# FPGA_QDRII.net
KiCad netlist of a schematic drawn in Altium Designer
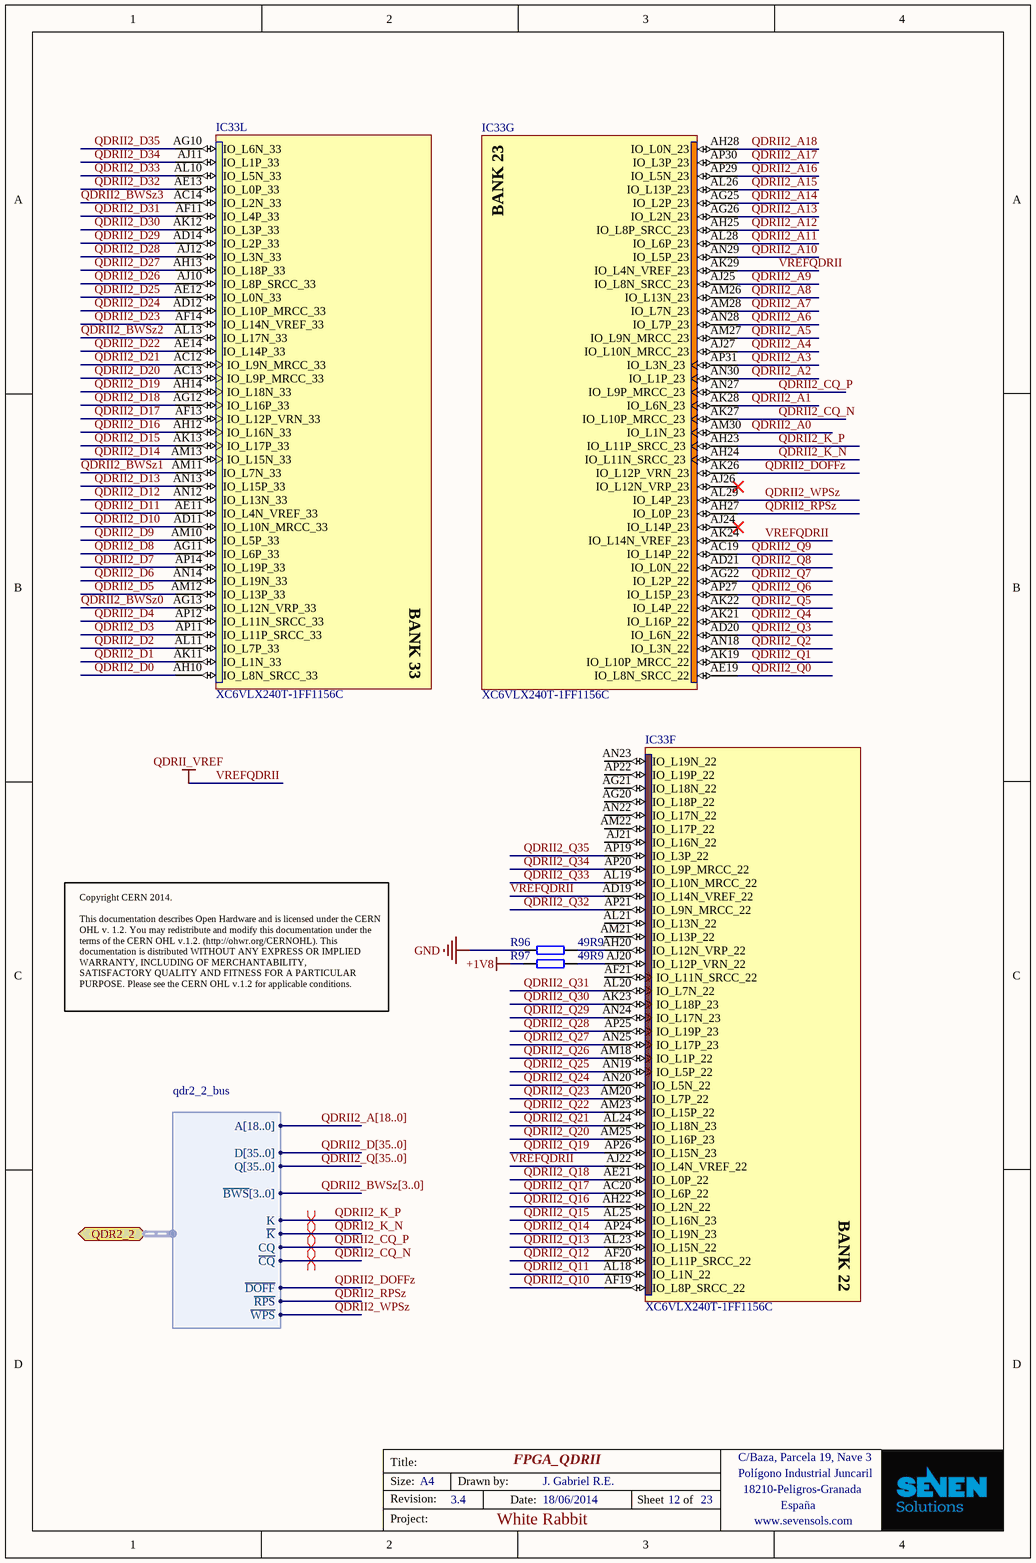
[diagram p0: FPGA_QDRII.SchDoc]

(export (version "E")
  (design (tool "Eeschema 10.0.6"))
  (components
    (comp (ref "IC33")
      (value "XC6VLX240T-1FF1156C")
      (footprint "FF1156")
      (fields (field (name "PUBLISHER") "Altium Limited"))
      (libsource (lib "") (part "XC6VLX240T-1FF1156C_1"))
    )
    (comp (ref "R96")
      (value "49R9")
      (footprint "0402")
      (description "SMD Resistor")
      (fields (field (name "TOLERANCE") "±1%") (field (name "Comment") "49R9 (not mounted)"))
      (libsource (lib "wr_switch") (part "RES_SMD"))
    )
    (comp (ref "R97")
      (value "49R9")
      (footprint "0402")
      (description "SMD Resistor")
      (fields (field (name "TOLERANCE") "±1%") (field (name "Comment") "49R9 (not mounted)"))
      (libsource (lib "wr_switch") (part "RES_SMD"))
    )
  )
  (nets
    (net (code "2") (name "+1V8") (class "Default")
      (node (ref "R97") (pin "2") (pinfunction "2_2") (pintype "passive"))
    )
    (net (code "4") (name "/QDRII2_A0") (class "Default")
      (node (ref "IC33") (pin "AM30") (pinfunction "IO_L1N_23_AM30") (pintype "bidirectional"))
    )
    (net (code "5") (name "/QDRII2_A1") (class "Default")
      (node (ref "IC33") (pin "AK28") (pinfunction "IO_L6N_23_AK28") (pintype "bidirectional"))
    )
    (net (code "6") (name "/QDRII2_A2") (class "Default")
      (node (ref "IC33") (pin "AN30") (pinfunction "IO_L1P_23_AN30") (pintype "bidirectional"))
    )
    (net (code "7") (name "/QDRII2_A3") (class "Default")
      (node (ref "IC33") (pin "AP31") (pinfunction "IO_L3N_23_AP31") (pintype "bidirectional"))
    )
    (net (code "8") (name "/QDRII2_A4") (class "Default")
      (node (ref "IC33") (pin "AJ27") (pinfunction "IO_L10N_MRCC_23_AJ27") (pintype "bidirectional"))
    )
    (net (code "9") (name "/QDRII2_A5") (class "Default")
      (node (ref "IC33") (pin "AM27") (pinfunction "IO_L9N_MRCC_23_AM27") (pintype "bidirectional"))
    )
    (net (code "10") (name "/QDRII2_A6") (class "Default")
      (node (ref "IC33") (pin "AN28") (pinfunction "IO_L7P_23_AN28") (pintype "bidirectional"))
    )
    (net (code "11") (name "/QDRII2_A7") (class "Default")
      (node (ref "IC33") (pin "AM28") (pinfunction "IO_L7N_23_AM28") (pintype "bidirectional"))
    )
    (net (code "12") (name "/QDRII2_A8") (class "Default")
      (node (ref "IC33") (pin "AM26") (pinfunction "IO_L13N_23_AM26") (pintype "bidirectional"))
    )
    (net (code "13") (name "/QDRII2_A9") (class "Default")
      (node (ref "IC33") (pin "AJ25") (pinfunction "IO_L8N_SRCC_23_AJ25") (pintype "bidirectional"))
    )
    (net (code "14") (name "/QDRII2_A10") (class "Default")
      (node (ref "IC33") (pin "AN29") (pinfunction "IO_L5P_23_AN29") (pintype "bidirectional"))
    )
    (net (code "15") (name "/QDRII2_A11") (class "Default")
      (node (ref "IC33") (pin "AL28") (pinfunction "IO_L6P_23_AL28") (pintype "bidirectional"))
    )
    (net (code "16") (name "/QDRII2_A12") (class "Default")
      (node (ref "IC33") (pin "AH25") (pinfunction "IO_L8P_SRCC_23_AH25") (pintype "bidirectional"))
    )
    (net (code "17") (name "/QDRII2_A13") (class "Default")
      (node (ref "IC33") (pin "AG26") (pinfunction "IO_L2N_23_AG26") (pintype "bidirectional"))
    )
    (net (code "18") (name "/QDRII2_A14") (class "Default")
      (node (ref "IC33") (pin "AG25") (pinfunction "IO_L2P_23_AG25") (pintype "bidirectional"))
    )
    (net (code "19") (name "/QDRII2_A15") (class "Default")
      (node (ref "IC33") (pin "AL26") (pinfunction "IO_L13P_23_AL26") (pintype "bidirectional"))
    )
    (net (code "20") (name "/QDRII2_A16") (class "Default")
      (node (ref "IC33") (pin "AP29") (pinfunction "IO_L5N_23_AP29") (pintype "bidirectional"))
    )
    (net (code "21") (name "/QDRII2_A17") (class "Default")
      (node (ref "IC33") (pin "AP30") (pinfunction "IO_L3P_23_AP30") (pintype "bidirectional"))
    )
    (net (code "22") (name "/QDRII2_A18") (class "Default")
      (node (ref "IC33") (pin "AH28") (pinfunction "IO_L0N_23_AH28") (pintype "bidirectional"))
    )
    (net (code "24") (name "/QDRII2_BWSz0") (class "Default")
      (node (ref "IC33") (pin "AG13") (pinfunction "IO_L12N_VRP_33_AG13") (pintype "bidirectional"))
    )
    (net (code "25") (name "/QDRII2_BWSz1") (class "Default")
      (node (ref "IC33") (pin "AM11") (pinfunction "IO_L7N_33_AM11") (pintype "bidirectional"))
    )
    (net (code "26") (name "/QDRII2_BWSz2") (class "Default")
      (node (ref "IC33") (pin "AL13") (pinfunction "IO_L17N_33_AL13") (pintype "bidirectional"))
    )
    (net (code "27") (name "/QDRII2_BWSz3") (class "Default")
      (node (ref "IC33") (pin "AC14") (pinfunction "IO_L2N_33_AC14") (pintype "bidirectional"))
    )
    (net (code "28") (name "/QDRII2_CQ_N") (class "Default")
      (node (ref "IC33") (pin "AK27") (pinfunction "IO_L10P_MRCC_23_AK27") (pintype "bidirectional"))
    )
    (net (code "29") (name "/QDRII2_CQ_P") (class "Default")
      (node (ref "IC33") (pin "AN27") (pinfunction "IO_L9P_MRCC_23_AN27") (pintype "bidirectional"))
    )
    (net (code "30") (name "/QDRII2_D0") (class "Default")
      (node (ref "IC33") (pin "AH10") (pinfunction "IO_L8N_SRCC_33_AH10") (pintype "bidirectional"))
    )
    (net (code "31") (name "/QDRII2_D1") (class "Default")
      (node (ref "IC33") (pin "AK11") (pinfunction "IO_L1N_33_AK11") (pintype "bidirectional"))
    )
    (net (code "32") (name "/QDRII2_D2") (class "Default")
      (node (ref "IC33") (pin "AL11") (pinfunction "IO_L7P_33_AL11") (pintype "bidirectional"))
    )
    (net (code "33") (name "/QDRII2_D3") (class "Default")
      (node (ref "IC33") (pin "AP11") (pinfunction "IO_L11P_SRCC_33_AP11") (pintype "bidirectional"))
    )
    (net (code "34") (name "/QDRII2_D4") (class "Default")
      (node (ref "IC33") (pin "AP12") (pinfunction "IO_L11N_SRCC_33_AP12") (pintype "bidirectional"))
    )
    (net (code "35") (name "/QDRII2_D5") (class "Default")
      (node (ref "IC33") (pin "AM12") (pinfunction "IO_L13P_33_AM12") (pintype "bidirectional"))
    )
    (net (code "36") (name "/QDRII2_D6") (class "Default")
      (node (ref "IC33") (pin "AN14") (pinfunction "IO_L19N_33_AN14") (pintype "bidirectional"))
    )
    (net (code "37") (name "/QDRII2_D7") (class "Default")
      (node (ref "IC33") (pin "AP14") (pinfunction "IO_L19P_33_AP14") (pintype "bidirectional"))
    )
    (net (code "38") (name "/QDRII2_D8") (class "Default")
      (node (ref "IC33") (pin "AG11") (pinfunction "IO_L6P_33_AG11") (pintype "bidirectional"))
    )
    (net (code "39") (name "/QDRII2_D9") (class "Default")
      (node (ref "IC33") (pin "AM10") (pinfunction "IO_L5P_33_AM10") (pintype "bidirectional"))
    )
    (net (code "40") (name "/QDRII2_D10") (class "Default")
      (node (ref "IC33") (pin "AD11") (pinfunction "IO_L10N_MRCC_33_AD11") (pintype "bidirectional"))
    )
    (net (code "41") (name "/QDRII2_D11") (class "Default")
      (node (ref "IC33") (pin "AE11") (pinfunction "IO_L4N_VREF_33_AE11") (pintype "bidirectional"))
    )
    (net (code "42") (name "/QDRII2_D12") (class "Default")
      (node (ref "IC33") (pin "AN12") (pinfunction "IO_L13N_33_AN12") (pintype "bidirectional"))
    )
    (net (code "43") (name "/QDRII2_D13") (class "Default")
      (node (ref "IC33") (pin "AN13") (pinfunction "IO_L15P_33_AN13") (pintype "bidirectional"))
    )
    (net (code "44") (name "/QDRII2_D14") (class "Default")
      (node (ref "IC33") (pin "AM13") (pinfunction "IO_L15N_33_AM13") (pintype "bidirectional"))
    )
    (net (code "45") (name "/QDRII2_D15") (class "Default")
      (node (ref "IC33") (pin "AK13") (pinfunction "IO_L17P_33_AK13") (pintype "bidirectional"))
    )
    (net (code "46") (name "/QDRII2_D16") (class "Default")
      (node (ref "IC33") (pin "AH12") (pinfunction "IO_L16N_33_AH12") (pintype "bidirectional"))
    )
    (net (code "47") (name "/QDRII2_D17") (class "Default")
      (node (ref "IC33") (pin "AF13") (pinfunction "IO_L12P_VRN_33_AF13") (pintype "bidirectional"))
    )
    (net (code "48") (name "/QDRII2_D18") (class "Default")
      (node (ref "IC33") (pin "AG12") (pinfunction "IO_L16P_33_AG12") (pintype "bidirectional"))
    )
    (net (code "49") (name "/QDRII2_D19") (class "Default")
      (node (ref "IC33") (pin "AH14") (pinfunction "IO_L18N_33_AH14") (pintype "bidirectional"))
    )
    (net (code "50") (name "/QDRII2_D20") (class "Default")
      (node (ref "IC33") (pin "AC13") (pinfunction "IO_L9P_MRCC_33_AC13") (pintype "bidirectional"))
    )
    (net (code "51") (name "/QDRII2_D21") (class "Default")
      (node (ref "IC33") (pin "AC12") (pinfunction "IO_L9N_MRCC_33_AC12") (pintype "bidirectional"))
    )
    (net (code "52") (name "/QDRII2_D22") (class "Default")
      (node (ref "IC33") (pin "AE14") (pinfunction "IO_L14P_33_AE14") (pintype "bidirectional"))
    )
    (net (code "53") (name "/QDRII2_D23") (class "Default")
      (node (ref "IC33") (pin "AF14") (pinfunction "IO_L14N_VREF_33_AF14") (pintype "bidirectional"))
    )
    (net (code "54") (name "/QDRII2_D24") (class "Default")
      (node (ref "IC33") (pin "AD12") (pinfunction "IO_L10P_MRCC_33_AD12") (pintype "bidirectional"))
    )
    (net (code "55") (name "/QDRII2_D25") (class "Default")
      (node (ref "IC33") (pin "AE12") (pinfunction "IO_L0N_33_AE12") (pintype "bidirectional"))
    )
    (net (code "56") (name "/QDRII2_D26") (class "Default")
      (node (ref "IC33") (pin "AJ10") (pinfunction "IO_L8P_SRCC_33_AJ10") (pintype "bidirectional"))
    )
    (net (code "57") (name "/QDRII2_D27") (class "Default")
      (node (ref "IC33") (pin "AH13") (pinfunction "IO_L18P_33_AH13") (pintype "bidirectional"))
    )
    (net (code "58") (name "/QDRII2_D28") (class "Default")
      (node (ref "IC33") (pin "AJ12") (pinfunction "IO_L3N_33_AJ12") (pintype "bidirectional"))
    )
    (net (code "59") (name "/QDRII2_D29") (class "Default")
      (node (ref "IC33") (pin "AD14") (pinfunction "IO_L2P_33_AD14") (pintype "bidirectional"))
    )
    (net (code "60") (name "/QDRII2_D30") (class "Default")
      (node (ref "IC33") (pin "AK12") (pinfunction "IO_L3P_33_AK12") (pintype "bidirectional"))
    )
    (net (code "61") (name "/QDRII2_D31") (class "Default")
      (node (ref "IC33") (pin "AF11") (pinfunction "IO_L4P_33_AF11") (pintype "bidirectional"))
    )
    (net (code "62") (name "/QDRII2_D32") (class "Default")
      (node (ref "IC33") (pin "AE13") (pinfunction "IO_L0P_33_AE13") (pintype "bidirectional"))
    )
    (net (code "63") (name "/QDRII2_D33") (class "Default")
      (node (ref "IC33") (pin "AL10") (pinfunction "IO_L5N_33_AL10") (pintype "bidirectional"))
    )
    (net (code "64") (name "/QDRII2_D34") (class "Default")
      (node (ref "IC33") (pin "AJ11") (pinfunction "IO_L1P_33_AJ11") (pintype "bidirectional"))
    )
    (net (code "65") (name "/QDRII2_D35") (class "Default")
      (node (ref "IC33") (pin "AG10") (pinfunction "IO_L6N_33_AG10") (pintype "bidirectional"))
    )
    (net (code "66") (name "/QDRII2_DOFFz") (class "Default")
      (node (ref "IC33") (pin "AK26") (pinfunction "IO_L12P_VRN_23_AK26") (pintype "bidirectional"))
    )
    (net (code "68") (name "/QDRII2_K_N") (class "Default")
      (node (ref "IC33") (pin "AH24") (pinfunction "IO_L11N_SRCC_23_AH24") (pintype "bidirectional"))
    )
    (net (code "69") (name "/QDRII2_K_P") (class "Default")
      (node (ref "IC33") (pin "AH23") (pinfunction "IO_L11P_SRCC_23_AH23") (pintype "bidirectional"))
    )
    (net (code "70") (name "/QDRII2_Q0") (class "Default")
      (node (ref "IC33") (pin "AE19") (pinfunction "IO_L8N_SRCC_22_AE19") (pintype "bidirectional"))
    )
    (net (code "71") (name "/QDRII2_Q1") (class "Default")
      (node (ref "IC33") (pin "AK19") (pinfunction "IO_L10P_MRCC_22_AK19") (pintype "bidirectional"))
    )
    (net (code "72") (name "/QDRII2_Q2") (class "Default")
      (node (ref "IC33") (pin "AN18") (pinfunction "IO_L3N_22_AN18") (pintype "bidirectional"))
    )
    (net (code "73") (name "/QDRII2_Q3") (class "Default")
      (node (ref "IC33") (pin "AD20") (pinfunction "IO_L6N_22_AD20") (pintype "bidirectional"))
    )
    (net (code "74") (name "/QDRII2_Q4") (class "Default")
      (node (ref "IC33") (pin "AK21") (pinfunction "IO_L16P_22_AK21") (pintype "bidirectional"))
    )
    (net (code "75") (name "/QDRII2_Q5") (class "Default")
      (node (ref "IC33") (pin "AK22") (pinfunction "IO_L4P_22_AK22") (pintype "bidirectional"))
    )
    (net (code "76") (name "/QDRII2_Q6") (class "Default")
      (node (ref "IC33") (pin "AP27") (pinfunction "IO_L15P_23_AP27") (pintype "bidirectional"))
    )
    (net (code "77") (name "/QDRII2_Q7") (class "Default")
      (node (ref "IC33") (pin "AG22") (pinfunction "IO_L2P_22_AG22") (pintype "bidirectional"))
    )
    (net (code "78") (name "/QDRII2_Q8") (class "Default")
      (node (ref "IC33") (pin "AD21") (pinfunction "IO_L0N_22_AD21") (pintype "bidirectional"))
    )
    (net (code "79") (name "/QDRII2_Q9") (class "Default")
      (node (ref "IC33") (pin "AC19") (pinfunction "IO_L14P_22_AC19") (pintype "bidirectional"))
    )
    (net (code "80") (name "/QDRII2_Q10") (class "Default")
      (node (ref "IC33") (pin "AF19") (pinfunction "IO_L8P_SRCC_22_AF19") (pintype "bidirectional"))
    )
    (net (code "81") (name "/QDRII2_Q11") (class "Default")
      (node (ref "IC33") (pin "AL18") (pinfunction "IO_L1N_22_AL18") (pintype "bidirectional"))
    )
    (net (code "82") (name "/QDRII2_Q12") (class "Default")
      (node (ref "IC33") (pin "AF20") (pinfunction "IO_L11P_SRCC_22_AF20") (pintype "bidirectional"))
    )
    (net (code "83") (name "/QDRII2_Q13") (class "Default")
      (node (ref "IC33") (pin "AL23") (pinfunction "IO_L15N_22_AL23") (pintype "bidirectional"))
    )
    (net (code "84") (name "/QDRII2_Q14") (class "Default")
      (node (ref "IC33") (pin "AP24") (pinfunction "IO_L19N_23_AP24") (pintype "bidirectional"))
    )
    (net (code "85") (name "/QDRII2_Q15") (class "Default")
      (node (ref "IC33") (pin "AL25") (pinfunction "IO_L16N_23_AL25") (pintype "bidirectional"))
    )
    (net (code "86") (name "/QDRII2_Q16") (class "Default")
      (node (ref "IC33") (pin "AH22") (pinfunction "IO_L2N_22_AH22") (pintype "bidirectional"))
    )
    (net (code "87") (name "/QDRII2_Q17") (class "Default")
      (node (ref "IC33") (pin "AC20") (pinfunction "IO_L6P_22_AC20") (pintype "bidirectional"))
    )
    (net (code "88") (name "/QDRII2_Q18") (class "Default")
      (node (ref "IC33") (pin "AE21") (pinfunction "IO_L0P_22_AE21") (pintype "bidirectional"))
    )
    (net (code "89") (name "/QDRII2_Q19") (class "Default")
      (node (ref "IC33") (pin "AP26") (pinfunction "IO_L15N_23_AP26") (pintype "bidirectional"))
    )
    (net (code "90") (name "/QDRII2_Q20") (class "Default")
      (node (ref "IC33") (pin "AM25") (pinfunction "IO_L16P_23_AM25") (pintype "bidirectional"))
    )
    (net (code "91") (name "/QDRII2_Q21") (class "Default")
      (node (ref "IC33") (pin "AL24") (pinfunction "IO_L18N_23_AL24") (pintype "bidirectional"))
    )
    (net (code "92") (name "/QDRII2_Q22") (class "Default")
      (node (ref "IC33") (pin "AM23") (pinfunction "IO_L15P_22_AM23") (pintype "bidirectional"))
    )
    (net (code "93") (name "/QDRII2_Q23") (class "Default")
      (node (ref "IC33") (pin "AM20") (pinfunction "IO_L7P_22_AM20") (pintype "bidirectional"))
    )
    (net (code "94") (name "/QDRII2_Q24") (class "Default")
      (node (ref "IC33") (pin "AN20") (pinfunction "IO_L5N_22_AN20") (pintype "bidirectional"))
    )
    (net (code "95") (name "/QDRII2_Q25") (class "Default")
      (node (ref "IC33") (pin "AN19") (pinfunction "IO_L5P_22_AN19") (pintype "bidirectional"))
    )
    (net (code "96") (name "/QDRII2_Q26") (class "Default")
      (node (ref "IC33") (pin "AM18") (pinfunction "IO_L1P_22_AM18") (pintype "bidirectional"))
    )
    (net (code "97") (name "/QDRII2_Q27") (class "Default")
      (node (ref "IC33") (pin "AN25") (pinfunction "IO_L17P_23_AN25") (pintype "bidirectional"))
    )
    (net (code "98") (name "/QDRII2_Q28") (class "Default")
      (node (ref "IC33") (pin "AP25") (pinfunction "IO_L19P_23_AP25") (pintype "bidirectional"))
    )
    (net (code "99") (name "/QDRII2_Q29") (class "Default")
      (node (ref "IC33") (pin "AN24") (pinfunction "IO_L17N_23_AN24") (pintype "bidirectional"))
    )
    (net (code "100") (name "/QDRII2_Q30") (class "Default")
      (node (ref "IC33") (pin "AK23") (pinfunction "IO_L18P_23_AK23") (pintype "bidirectional"))
    )
    (net (code "101") (name "/QDRII2_Q31") (class "Default")
      (node (ref "IC33") (pin "AL20") (pinfunction "IO_L7N_22_AL20") (pintype "bidirectional"))
    )
    (net (code "102") (name "/QDRII2_Q32") (class "Default")
      (node (ref "IC33") (pin "AP21") (pinfunction "IO_L9N_MRCC_22_AP21") (pintype "bidirectional"))
    )
    (net (code "103") (name "/QDRII2_Q33") (class "Default")
      (node (ref "IC33") (pin "AL19") (pinfunction "IO_L10N_MRCC_22_AL19") (pintype "bidirectional"))
    )
    (net (code "104") (name "/QDRII2_Q34") (class "Default")
      (node (ref "IC33") (pin "AP20") (pinfunction "IO_L9P_MRCC_22_AP20") (pintype "bidirectional"))
    )
    (net (code "105") (name "/QDRII2_Q35") (class "Default")
      (node (ref "IC33") (pin "AP19") (pinfunction "IO_L3P_22_AP19") (pintype "bidirectional"))
    )
    (net (code "107") (name "/QDRII2_RPSz") (class "Default")
      (node (ref "IC33") (pin "AH27") (pinfunction "IO_L0P_23_AH27") (pintype "bidirectional"))
    )
    (net (code "108") (name "/QDRII2_WPSz") (class "Default")
      (node (ref "IC33") (pin "AL29") (pinfunction "IO_L4P_23_AL29") (pintype "bidirectional"))
    )
    (net (code "110") (name "GND") (class "Default")
      (node (ref "R96") (pin "2") (pinfunction "2_2") (pintype "passive"))
    )
    (net (code "111") (name "Net-(IC33F-IO_L12N_VRP_22)") (class "Default")
      (node (ref "IC33") (pin "AH20") (pinfunction "IO_L12N_VRP_22_AH20") (pintype "bidirectional"))
      (node (ref "R96") (pin "1") (pinfunction "1_1") (pintype "passive"))
    )
    (net (code "112") (name "Net-(IC33F-IO_L12P_VRN_22)") (class "Default")
      (node (ref "IC33") (pin "AJ20") (pinfunction "IO_L12P_VRN_22_AJ20") (pintype "bidirectional"))
      (node (ref "R97") (pin "1") (pinfunction "1_1") (pintype "passive"))
    )
    (net (code "113") (name "QDRII_VREF") (class "Default")
      (node (ref "IC33") (pin "AD19") (pinfunction "IO_L14N_VREF_22_AD19") (pintype "bidirectional"))
      (node (ref "IC33") (pin "AJ22") (pinfunction "IO_L4N_VREF_22_AJ22") (pintype "bidirectional"))
      (node (ref "IC33") (pin "AK24") (pinfunction "IO_L14N_VREF_23_AK24") (pintype "bidirectional"))
      (node (ref "IC33") (pin "AK29") (pinfunction "IO_L4N_VREF_23_AK29") (pintype "bidirectional"))
    )
    (net (code "114") (name "unconnected-(IC33F-IO_L11N_SRCC_22-PadAF21)") (class "Default")
      (node (ref "IC33") (pin "AF21") (pinfunction "IO_L11N_SRCC_22_AF21") (pintype "bidirectional"))
    )
    (net (code "115") (name "unconnected-(IC33F-IO_L13N_22-PadAL21)") (class "Default")
      (node (ref "IC33") (pin "AL21") (pinfunction "IO_L13N_22_AL21") (pintype "bidirectional"))
    )
    (net (code "116") (name "unconnected-(IC33F-IO_L13P_22-PadAM21)") (class "Default")
      (node (ref "IC33") (pin "AM21") (pinfunction "IO_L13P_22_AM21") (pintype "bidirectional"))
    )
    (net (code "117") (name "unconnected-(IC33F-IO_L16N_22-PadAJ21)") (class "Default")
      (node (ref "IC33") (pin "AJ21") (pinfunction "IO_L16N_22_AJ21") (pintype "bidirectional"))
    )
    (net (code "118") (name "unconnected-(IC33F-IO_L17N_22-PadAN22)") (class "Default")
      (node (ref "IC33") (pin "AN22") (pinfunction "IO_L17N_22_AN22") (pintype "bidirectional"))
    )
    (net (code "119") (name "unconnected-(IC33F-IO_L17P_22-PadAM22)") (class "Default")
      (node (ref "IC33") (pin "AM22") (pinfunction "IO_L17P_22_AM22") (pintype "bidirectional"))
    )
    (net (code "120") (name "unconnected-(IC33F-IO_L18N_22-PadAG21)") (class "Default")
      (node (ref "IC33") (pin "AG21") (pinfunction "IO_L18N_22_AG21") (pintype "bidirectional"))
    )
    (net (code "121") (name "unconnected-(IC33F-IO_L18P_22-PadAG20)") (class "Default")
      (node (ref "IC33") (pin "AG20") (pinfunction "IO_L18P_22_AG20") (pintype "bidirectional"))
    )
    (net (code "122") (name "unconnected-(IC33F-IO_L19N_22-PadAN23)") (class "Default")
      (node (ref "IC33") (pin "AN23") (pinfunction "IO_L19N_22_AN23") (pintype "bidirectional"))
    )
    (net (code "123") (name "unconnected-(IC33F-IO_L19P_22-PadAP22)") (class "Default")
      (node (ref "IC33") (pin "AP22") (pinfunction "IO_L19P_22_AP22") (pintype "bidirectional"))
    )
    (net (code "124") (name "unconnected-(IC33G-IO_L12N_VRP_23-PadAJ26)") (class "Default")
      (node (ref "IC33") (pin "AJ26") (pinfunction "IO_L12N_VRP_23_AJ26") (pintype "bidirectional+no_connect"))
    )
    (net (code "125") (name "unconnected-(IC33G-IO_L14P_23-PadAJ24)") (class "Default")
      (node (ref "IC33") (pin "AJ24") (pinfunction "IO_L14P_23_AJ24") (pintype "bidirectional+no_connect"))
    )
  )
)
